# PR04.net
KiCad netlist of a schematic drawn in EAGLE
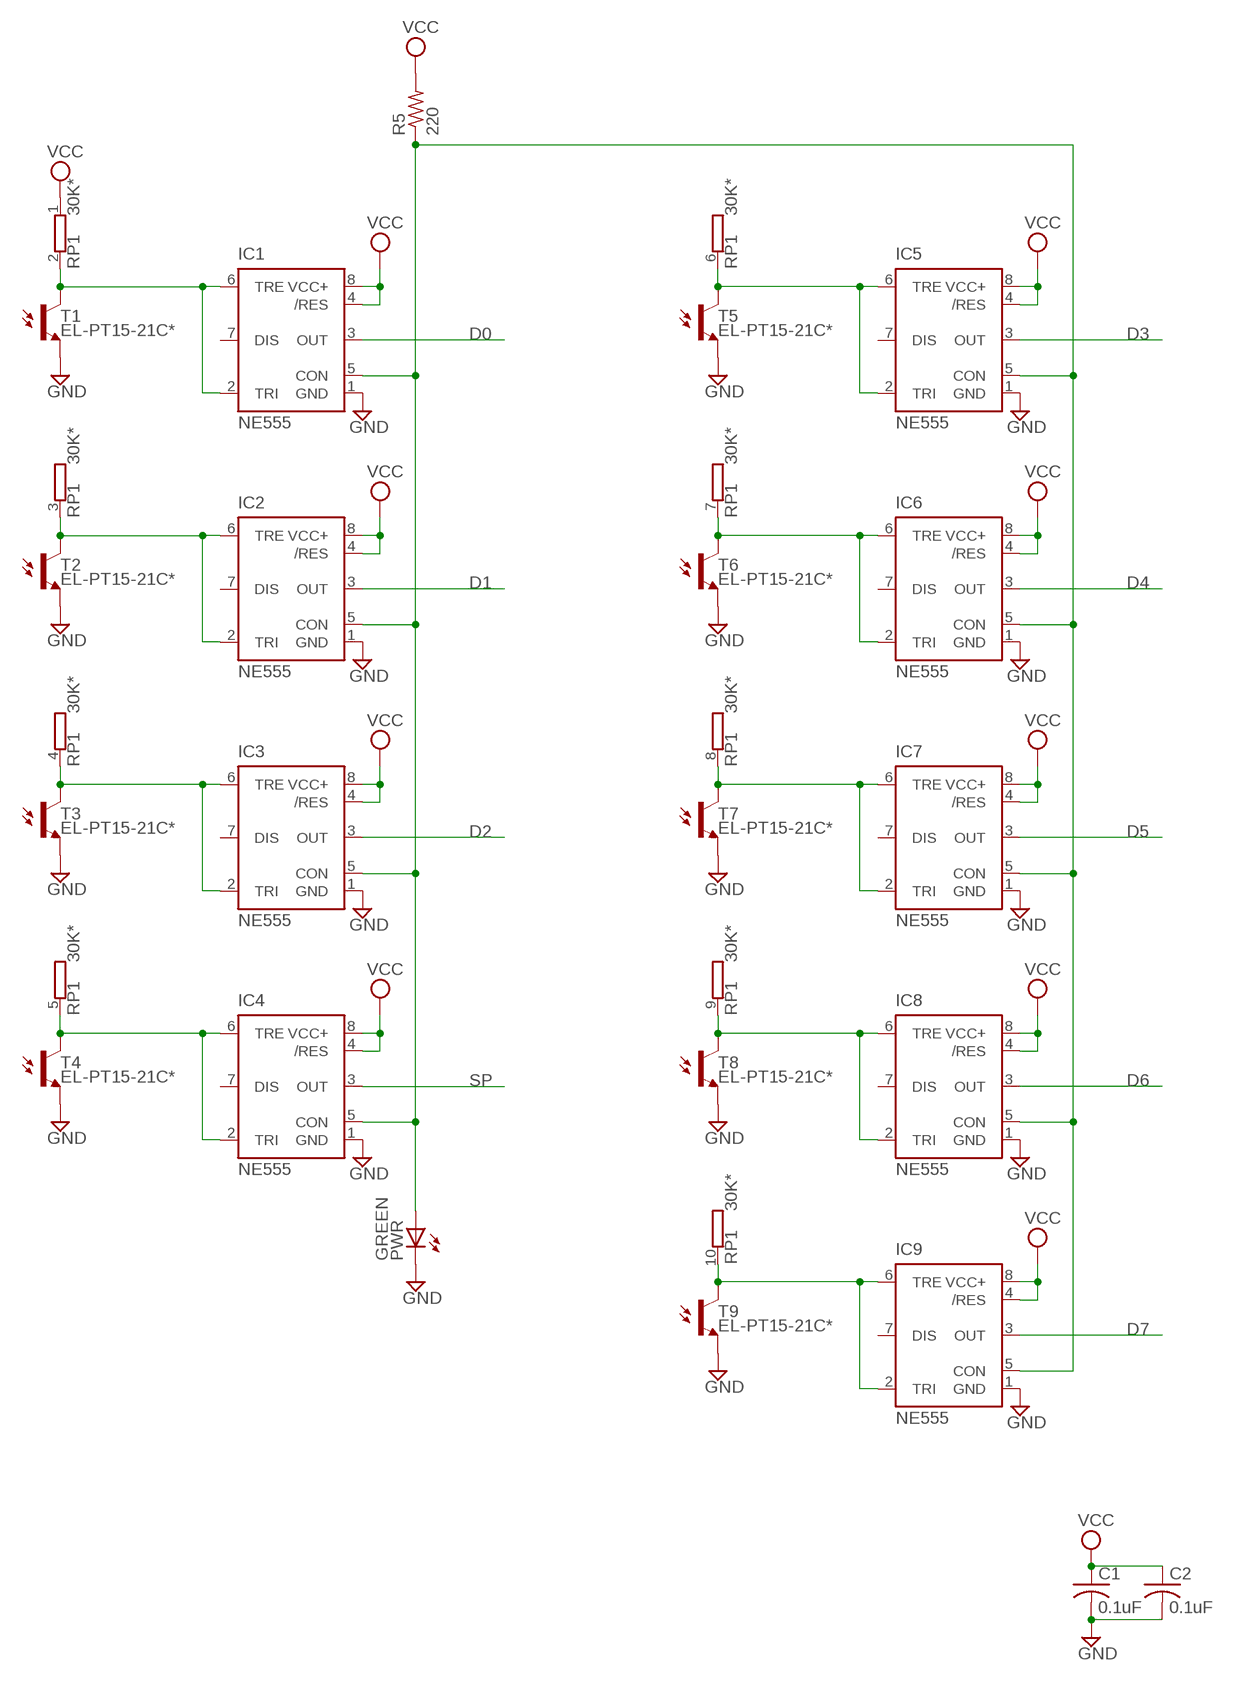
[diagram p0: schematic, sheet 1, part 1 of 2]
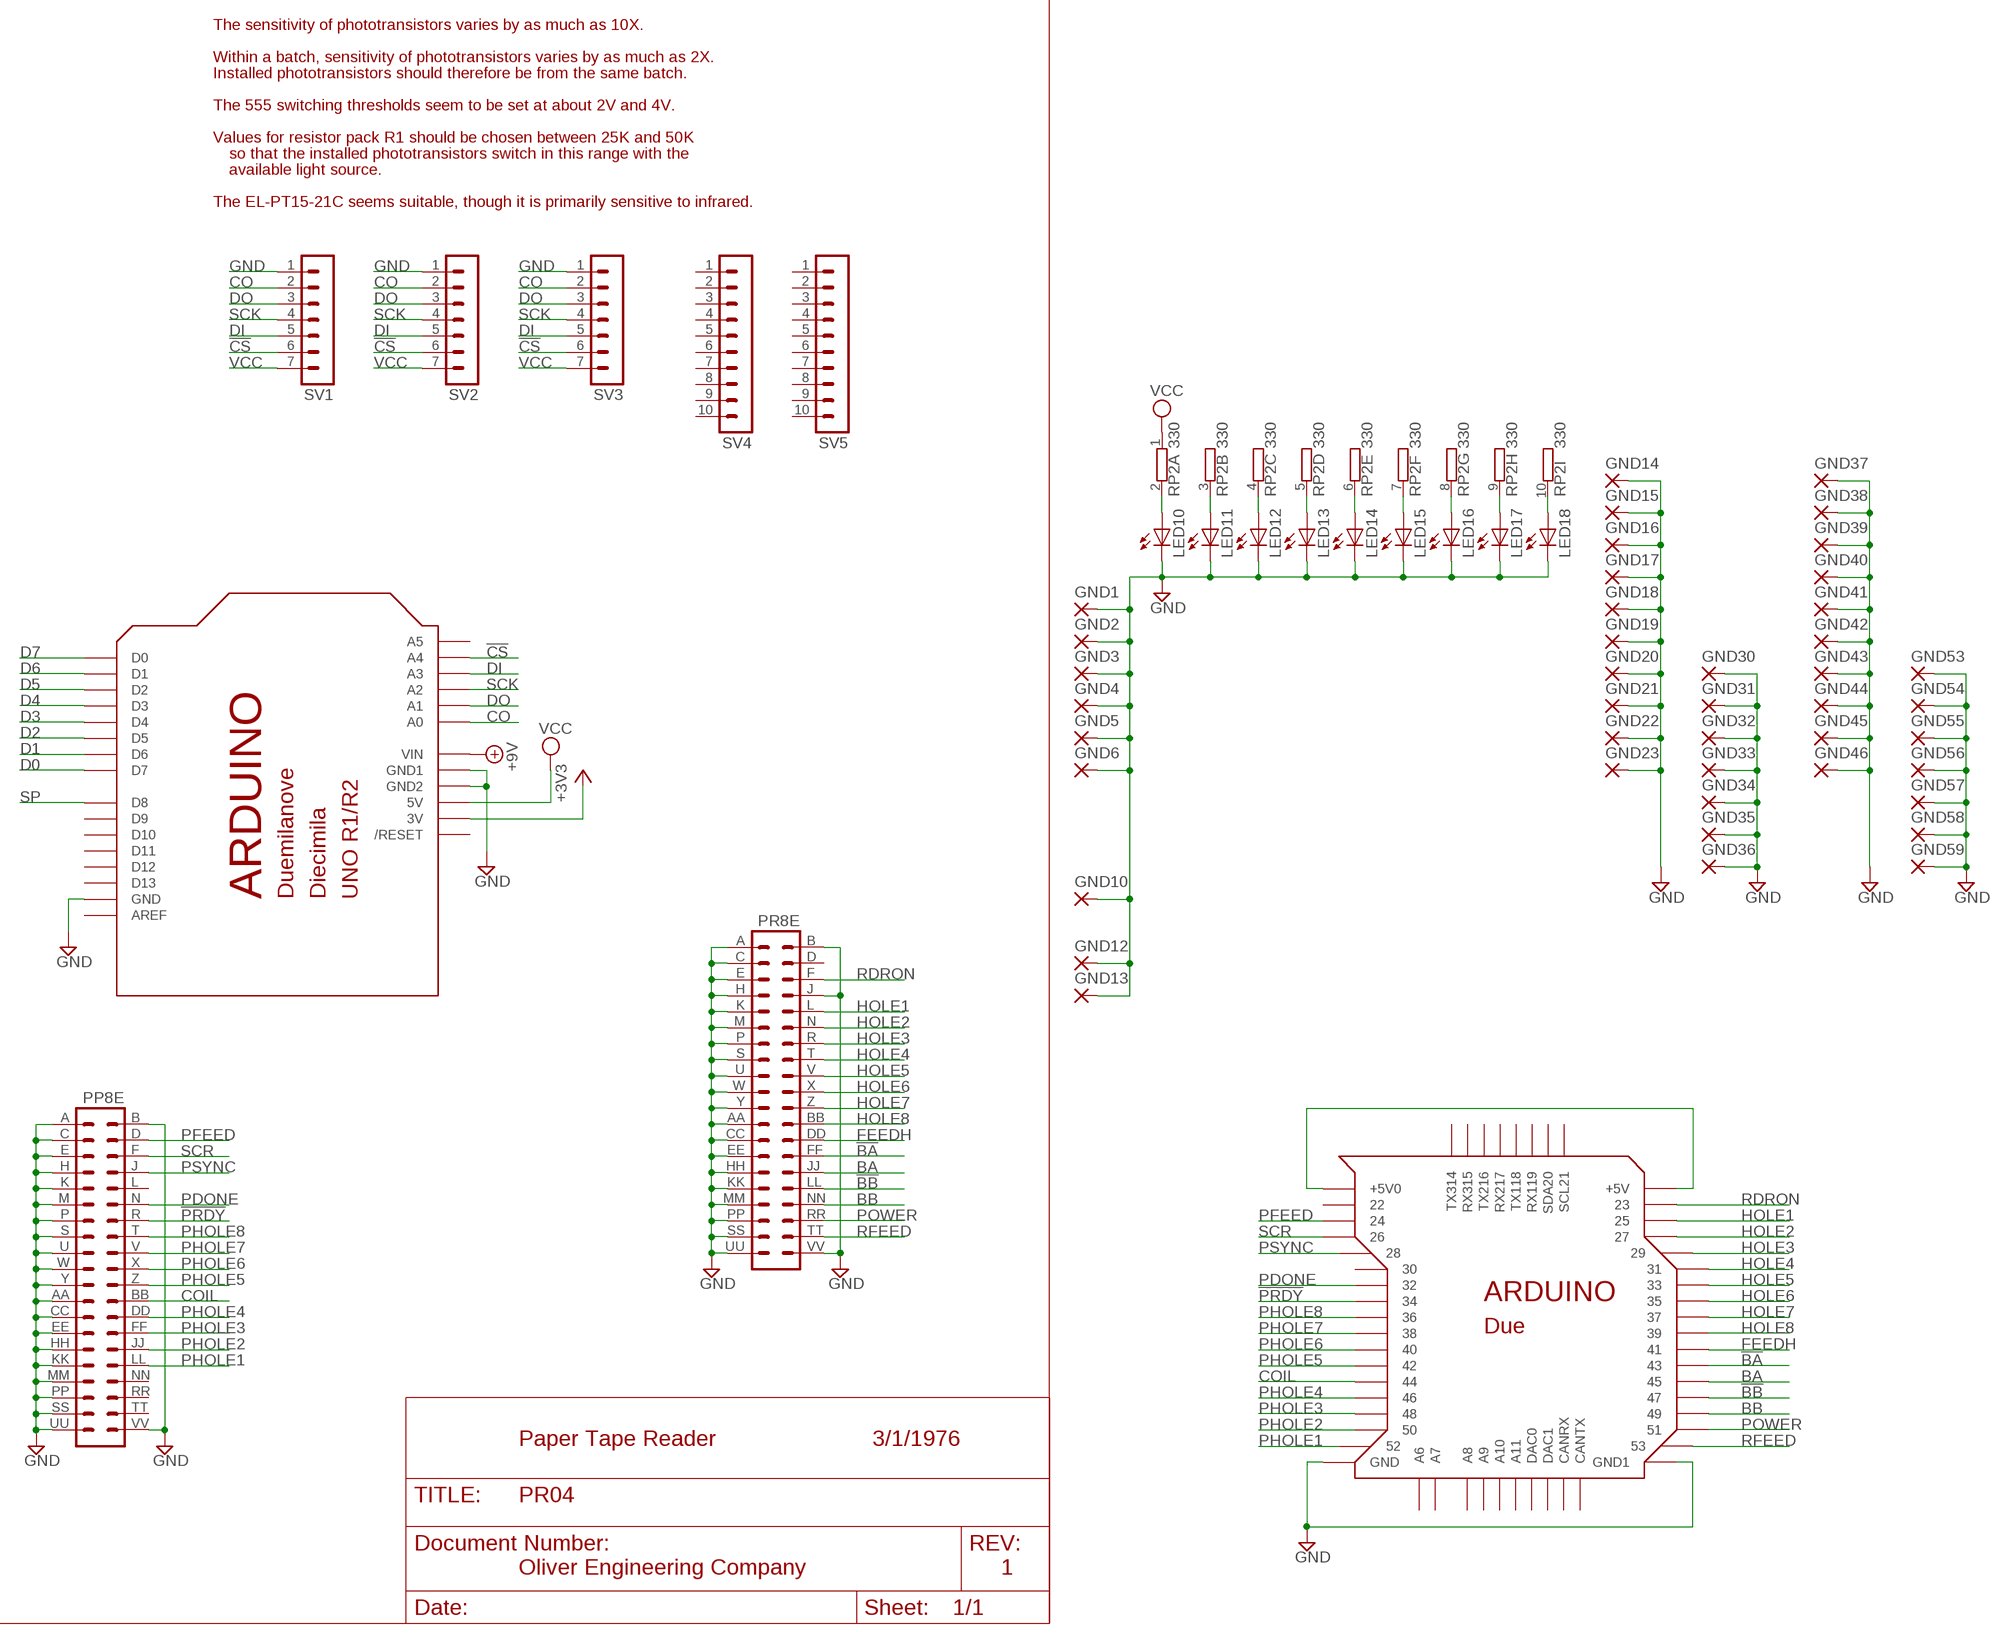
[diagram p1: schematic, sheet 1, part 2 of 2]

(export (version "E")
  (design (tool "Eeschema 10.0.6"))
  (components
    (comp (ref "C1")
      (value "0.1uF")
      (footprint "eagle-import:C050-030X075")
      (libsource (lib "eagle-import") (part "C-US050-030X075"))
    )
    (comp (ref "C2")
      (value "0.1uF")
      (footprint "eagle-import:C050-030X075")
      (libsource (lib "eagle-import") (part "C-US050-030X075"))
    )
    (comp (ref "GND1")
      (value "2,15/1,0")
      (footprint "eagle-import:2,15_1,0")
      (libsource (lib "eagle-import") (part "2,15/1,0"))
    )
    (comp (ref "GND2")
      (value "2,15/1,0")
      (footprint "eagle-import:2,15_1,0")
      (libsource (lib "eagle-import") (part "2,15/1,0"))
    )
    (comp (ref "GND3")
      (value "2,15/1,0")
      (footprint "eagle-import:2,15_1,0")
      (libsource (lib "eagle-import") (part "2,15/1,0"))
    )
    (comp (ref "GND4")
      (value "2,15/1,0")
      (footprint "eagle-import:2,15_1,0")
      (libsource (lib "eagle-import") (part "2,15/1,0"))
    )
    (comp (ref "GND5")
      (value "2,15/1,0")
      (footprint "eagle-import:2,15_1,0")
      (libsource (lib "eagle-import") (part "2,15/1,0"))
    )
    (comp (ref "GND6")
      (value "2,15/1,0")
      (footprint "eagle-import:2,15_1,0")
      (libsource (lib "eagle-import") (part "2,15/1,0"))
    )
    (comp (ref "GND10")
      (value "2,15/1,0")
      (footprint "eagle-import:2,15_1,0")
      (libsource (lib "eagle-import") (part "2,15/1,0"))
    )
    (comp (ref "GND12")
      (value "2,15/1,0")
      (footprint "eagle-import:2,15_1,0")
      (libsource (lib "eagle-import") (part "2,15/1,0"))
    )
    (comp (ref "GND13")
      (value "2,15/1,0")
      (footprint "eagle-import:2,15_1,0")
      (libsource (lib "eagle-import") (part "2,15/1,0"))
    )
    (comp (ref "GND14")
      (value "2,15/1,0")
      (footprint "eagle-import:2,15_1,0")
      (libsource (lib "eagle-import") (part "2,15/1,0"))
    )
    (comp (ref "GND15")
      (value "2,15/1,0")
      (footprint "eagle-import:2,15_1,0")
      (libsource (lib "eagle-import") (part "2,15/1,0"))
    )
    (comp (ref "GND16")
      (value "2,15/1,0")
      (footprint "eagle-import:2,15_1,0")
      (libsource (lib "eagle-import") (part "2,15/1,0"))
    )
    (comp (ref "GND17")
      (value "2,15/1,0")
      (footprint "eagle-import:2,15_1,0")
      (libsource (lib "eagle-import") (part "2,15/1,0"))
    )
    (comp (ref "GND18")
      (value "2,15/1,0")
      (footprint "eagle-import:2,15_1,0")
      (libsource (lib "eagle-import") (part "2,15/1,0"))
    )
    (comp (ref "GND19")
      (value "2,15/1,0")
      (footprint "eagle-import:2,15_1,0")
      (libsource (lib "eagle-import") (part "2,15/1,0"))
    )
    (comp (ref "GND20")
      (value "2,15/1,0")
      (footprint "eagle-import:2,15_1,0")
      (libsource (lib "eagle-import") (part "2,15/1,0"))
    )
    (comp (ref "GND21")
      (value "2,15/1,0")
      (footprint "eagle-import:2,15_1,0")
      (libsource (lib "eagle-import") (part "2,15/1,0"))
    )
    (comp (ref "GND22")
      (value "2,15/1,0")
      (footprint "eagle-import:2,15_1,0")
      (libsource (lib "eagle-import") (part "2,15/1,0"))
    )
    (comp (ref "GND23")
      (value "2,15/1,0")
      (footprint "eagle-import:2,15_1,0")
      (libsource (lib "eagle-import") (part "2,15/1,0"))
    )
    (comp (ref "GND30")
      (value "2,15/1,0")
      (footprint "eagle-import:2,15_1,0")
      (libsource (lib "eagle-import") (part "2,15/1,0"))
    )
    (comp (ref "GND31")
      (value "2,15/1,0")
      (footprint "eagle-import:2,15_1,0")
      (libsource (lib "eagle-import") (part "2,15/1,0"))
    )
    (comp (ref "GND32")
      (value "2,15/1,0")
      (footprint "eagle-import:2,15_1,0")
      (libsource (lib "eagle-import") (part "2,15/1,0"))
    )
    (comp (ref "GND33")
      (value "2,15/1,0")
      (footprint "eagle-import:2,15_1,0")
      (libsource (lib "eagle-import") (part "2,15/1,0"))
    )
    (comp (ref "GND34")
      (value "2,15/1,0")
      (footprint "eagle-import:2,15_1,0")
      (libsource (lib "eagle-import") (part "2,15/1,0"))
    )
    (comp (ref "GND35")
      (value "2,15/1,0")
      (footprint "eagle-import:2,15_1,0")
      (libsource (lib "eagle-import") (part "2,15/1,0"))
    )
    (comp (ref "GND36")
      (value "2,15/1,0")
      (footprint "eagle-import:2,15_1,0")
      (libsource (lib "eagle-import") (part "2,15/1,0"))
    )
    (comp (ref "GND37")
      (value "2,15/1,0")
      (footprint "eagle-import:2,15_1,0")
      (libsource (lib "eagle-import") (part "2,15/1,0"))
    )
    (comp (ref "GND38")
      (value "2,15/1,0")
      (footprint "eagle-import:2,15_1,0")
      (libsource (lib "eagle-import") (part "2,15/1,0"))
    )
    (comp (ref "GND39")
      (value "2,15/1,0")
      (footprint "eagle-import:2,15_1,0")
      (libsource (lib "eagle-import") (part "2,15/1,0"))
    )
    (comp (ref "GND40")
      (value "2,15/1,0")
      (footprint "eagle-import:2,15_1,0")
      (libsource (lib "eagle-import") (part "2,15/1,0"))
    )
    (comp (ref "GND41")
      (value "2,15/1,0")
      (footprint "eagle-import:2,15_1,0")
      (libsource (lib "eagle-import") (part "2,15/1,0"))
    )
    (comp (ref "GND42")
      (value "2,15/1,0")
      (footprint "eagle-import:2,15_1,0")
      (libsource (lib "eagle-import") (part "2,15/1,0"))
    )
    (comp (ref "GND43")
      (value "2,15/1,0")
      (footprint "eagle-import:2,15_1,0")
      (libsource (lib "eagle-import") (part "2,15/1,0"))
    )
    (comp (ref "GND44")
      (value "2,15/1,0")
      (footprint "eagle-import:2,15_1,0")
      (libsource (lib "eagle-import") (part "2,15/1,0"))
    )
    (comp (ref "GND45")
      (value "2,15/1,0")
      (footprint "eagle-import:2,15_1,0")
      (libsource (lib "eagle-import") (part "2,15/1,0"))
    )
    (comp (ref "GND46")
      (value "2,15/1,0")
      (footprint "eagle-import:2,15_1,0")
      (libsource (lib "eagle-import") (part "2,15/1,0"))
    )
    (comp (ref "GND53")
      (value "2,15/1,0")
      (footprint "eagle-import:2,15_1,0")
      (libsource (lib "eagle-import") (part "2,15/1,0"))
    )
    (comp (ref "GND54")
      (value "2,15/1,0")
      (footprint "eagle-import:2,15_1,0")
      (libsource (lib "eagle-import") (part "2,15/1,0"))
    )
    (comp (ref "GND55")
      (value "2,15/1,0")
      (footprint "eagle-import:2,15_1,0")
      (libsource (lib "eagle-import") (part "2,15/1,0"))
    )
    (comp (ref "GND56")
      (value "2,15/1,0")
      (footprint "eagle-import:2,15_1,0")
      (libsource (lib "eagle-import") (part "2,15/1,0"))
    )
    (comp (ref "GND57")
      (value "2,15/1,0")
      (footprint "eagle-import:2,15_1,0")
      (libsource (lib "eagle-import") (part "2,15/1,0"))
    )
    (comp (ref "GND58")
      (value "2,15/1,0")
      (footprint "eagle-import:2,15_1,0")
      (libsource (lib "eagle-import") (part "2,15/1,0"))
    )
    (comp (ref "GND59")
      (value "2,15/1,0")
      (footprint "eagle-import:2,15_1,0")
      (libsource (lib "eagle-import") (part "2,15/1,0"))
    )
    (comp (ref "IC1")
      (value "NE555")
      (footprint "eagle-import:DIL-08")
      (fields (field (name "MF") "Arrow Electronics") (field (name "MPN") "NE555N"))
      (libsource (lib "eagle-import") (part "NE555"))
    )
    (comp (ref "IC2")
      (value "NE555")
      (footprint "eagle-import:DIL-08")
      (fields (field (name "MF") "Arrow Electronics") (field (name "MPN") "NE555N"))
      (libsource (lib "eagle-import") (part "NE555"))
    )
    (comp (ref "IC3")
      (value "NE555")
      (footprint "eagle-import:DIL-08")
      (fields (field (name "MF") "Arrow Electronics") (field (name "MPN") "NE555N"))
      (libsource (lib "eagle-import") (part "NE555"))
    )
    (comp (ref "IC4")
      (value "NE555")
      (footprint "eagle-import:DIL-08")
      (fields (field (name "MF") "Arrow Electronics") (field (name "MPN") "NE555N"))
      (libsource (lib "eagle-import") (part "NE555"))
    )
    (comp (ref "IC5")
      (value "NE555")
      (footprint "eagle-import:DIL-08")
      (fields (field (name "MF") "Arrow Electronics") (field (name "MPN") "NE555N"))
      (libsource (lib "eagle-import") (part "NE555"))
    )
    (comp (ref "IC6")
      (value "NE555")
      (footprint "eagle-import:DIL-08")
      (fields (field (name "MF") "Arrow Electronics") (field (name "MPN") "NE555N"))
      (libsource (lib "eagle-import") (part "NE555"))
    )
    (comp (ref "IC7")
      (value "NE555")
      (footprint "eagle-import:DIL-08")
      (fields (field (name "MF") "Arrow Electronics") (field (name "MPN") "NE555N"))
      (libsource (lib "eagle-import") (part "NE555"))
    )
    (comp (ref "IC8")
      (value "NE555")
      (footprint "eagle-import:DIL-08")
      (fields (field (name "MF") "Arrow Electronics") (field (name "MPN") "NE555N"))
      (libsource (lib "eagle-import") (part "NE555"))
    )
    (comp (ref "IC9")
      (value "NE555")
      (footprint "eagle-import:DIL-08")
      (fields (field (name "MF") "Arrow Electronics") (field (name "MPN") "NE555N"))
      (libsource (lib "eagle-import") (part "NE555"))
    )
    (comp (ref "LED10")
      (value "LEDCHIPLED_1206")
      (footprint "eagle-import:CHIPLED_1206")
      (libsource (lib "eagle-import") (part "opto_LEDCHIPLED_1206"))
    )
    (comp (ref "LED11")
      (value "LEDCHIPLED_1206")
      (footprint "eagle-import:CHIPLED_1206")
      (libsource (lib "eagle-import") (part "opto_LEDCHIPLED_1206"))
    )
    (comp (ref "LED12")
      (value "LEDCHIPLED_1206")
      (footprint "eagle-import:CHIPLED_1206")
      (libsource (lib "eagle-import") (part "opto_LEDCHIPLED_1206"))
    )
    (comp (ref "LED13")
      (value "LEDCHIPLED_1206")
      (footprint "eagle-import:CHIPLED_1206")
      (libsource (lib "eagle-import") (part "opto_LEDCHIPLED_1206"))
    )
    (comp (ref "LED14")
      (value "LEDCHIPLED_1206")
      (footprint "eagle-import:CHIPLED_1206")
      (libsource (lib "eagle-import") (part "opto_LEDCHIPLED_1206"))
    )
    (comp (ref "LED15")
      (value "LEDCHIPLED_1206")
      (footprint "eagle-import:CHIPLED_1206")
      (libsource (lib "eagle-import") (part "opto_LEDCHIPLED_1206"))
    )
    (comp (ref "LED16")
      (value "LEDCHIPLED_1206")
      (footprint "eagle-import:CHIPLED_1206")
      (libsource (lib "eagle-import") (part "opto_LEDCHIPLED_1206"))
    )
    (comp (ref "LED17")
      (value "LEDCHIPLED_1206")
      (footprint "eagle-import:CHIPLED_1206")
      (libsource (lib "eagle-import") (part "opto_LEDCHIPLED_1206"))
    )
    (comp (ref "LED18")
      (value "LEDCHIPLED_1206")
      (footprint "eagle-import:CHIPLED_1206")
      (libsource (lib "eagle-import") (part "opto_LEDCHIPLED_1206"))
    )
    (comp (ref "PP8E")
      (value "DEC40PINV")
      (footprint "eagle-import:DEC40PINV")
      (libsource (lib "eagle-import") (part "DEC40PINV"))
    )
    (comp (ref "PR8E")
      (value "DEC40PINV")
      (footprint "eagle-import:DEC40PINV")
      (libsource (lib "eagle-import") (part "DEC40PINV"))
    )
    (comp (ref "PWR")
      (value "GREEN")
      (footprint "eagle-import:LED3MM")
      (libsource (lib "eagle-import") (part "LED3MM"))
    )
    (comp (ref "R5")
      (value "220")
      (footprint "eagle-import:0207_10")
      (libsource (lib "eagle-import") (part "R-US_0207/10"))
    )
    (comp (ref "RP1")
      (value "30K*")
      (footprint "eagle-import:SIL10")
      (libsource (lib "eagle-import") (part "GE09RP"))
    )
    (comp (ref "RP2")
      (value "330")
      (footprint "eagle-import:SIL10")
      (libsource (lib "eagle-import") (part "GE09R"))
    )
    (comp (ref "SV1")
      (value "MA07-1")
      (footprint "eagle-import:MA07-1")
      (libsource (lib "eagle-import") (part "MA07-1"))
    )
    (comp (ref "SV2")
      (value "MA07-1")
      (footprint "eagle-import:MA07-1")
      (libsource (lib "eagle-import") (part "MA07-1"))
    )
    (comp (ref "SV3")
      (value "MA07-1")
      (footprint "eagle-import:MA07-1")
      (libsource (lib "eagle-import") (part "MA07-1"))
    )
    (comp (ref "SV4")
      (value "MA10-1")
      (footprint "eagle-import:MA10-1")
      (libsource (lib "eagle-import") (part "MA10-1"))
    )
    (comp (ref "SV5")
      (value "MA10-1")
      (footprint "eagle-import:MA10-1")
      (libsource (lib "eagle-import") (part "MA10-1"))
    )
    (comp (ref "T1")
      (value "EL-PT15-21C*")
      (footprint "eagle-import:CHIPLED_1206")
      (libsource (lib "eagle-import") (part "PHOTOTRANSISTOR"))
    )
    (comp (ref "T2")
      (value "EL-PT15-21C*")
      (footprint "eagle-import:CHIPLED_1206")
      (libsource (lib "eagle-import") (part "PHOTOTRANSISTOR"))
    )
    (comp (ref "T3")
      (value "EL-PT15-21C*")
      (footprint "eagle-import:CHIPLED_1206")
      (libsource (lib "eagle-import") (part "PHOTOTRANSISTOR"))
    )
    (comp (ref "T4")
      (value "EL-PT15-21C*")
      (footprint "eagle-import:CHIPLED_1206")
      (libsource (lib "eagle-import") (part "PHOTOTRANSISTOR"))
    )
    (comp (ref "T5")
      (value "EL-PT15-21C*")
      (footprint "eagle-import:CHIPLED_1206")
      (libsource (lib "eagle-import") (part "PHOTOTRANSISTOR"))
    )
    (comp (ref "T6")
      (value "EL-PT15-21C*")
      (footprint "eagle-import:CHIPLED_1206")
      (libsource (lib "eagle-import") (part "PHOTOTRANSISTOR"))
    )
    (comp (ref "T7")
      (value "EL-PT15-21C*")
      (footprint "eagle-import:CHIPLED_1206")
      (libsource (lib "eagle-import") (part "PHOTOTRANSISTOR"))
    )
    (comp (ref "T8")
      (value "EL-PT15-21C*")
      (footprint "eagle-import:CHIPLED_1206")
      (libsource (lib "eagle-import") (part "PHOTOTRANSISTOR"))
    )
    (comp (ref "T9")
      (value "EL-PT15-21C*")
      (footprint "eagle-import:CHIPLED_1206")
      (libsource (lib "eagle-import") (part "PHOTOTRANSISTOR"))
    )
    (comp (ref "U$2")
      (value "ARDUINO-X")
      (footprint "eagle-import:ARDUINO_DUE_SHIELD")
      (libsource (lib "eagle-import") (part "ARDUINO-X"))
    )
  )
  (nets
    (net (code "1") (name "+3V3") (class "Default")
      (node (ref "U$2") (pin "3V3") (pinfunction "3V_3V3") (pintype "power_in"))
    )
    (net (code "2") (name "+9V") (class "Default")
      (node (ref "U$2") (pin "VIN") (pinfunction "VIN_VIN") (pintype "power_in"))
    )
    (net (code "3") (name "/BA") (class "Default")
      (node (ref "PR8E") (pin "JJ") (pinfunction "30_JJ") (pintype "bidirectional"))
      (node (ref "U$2") (pin "45") (pinfunction "45_45") (pintype "bidirectional"))
    )
    (net (code "4") (name "/BB") (class "Default")
      (node (ref "PR8E") (pin "NN") (pinfunction "34_NN") (pintype "bidirectional"))
      (node (ref "U$2") (pin "49") (pinfunction "49_49") (pintype "bidirectional"))
    )
    (net (code "5") (name "/CO") (class "Default")
      (node (ref "SV1") (pin "2") (pinfunction "2_2") (pintype "passive"))
      (node (ref "SV2") (pin "2") (pinfunction "2_2") (pintype "passive"))
      (node (ref "SV3") (pin "2") (pinfunction "2_2") (pintype "passive"))
      (node (ref "U$2") (pin "A0") (pinfunction "A0_A0") (pintype "bidirectional"))
    )
    (net (code "6") (name "/COIL") (class "Default")
      (node (ref "PP8E") (pin "BB") (pinfunction "24_BB") (pintype "bidirectional"))
      (node (ref "U$2") (pin "44") (pinfunction "44_44") (pintype "bidirectional"))
    )
    (net (code "7") (name "/D0") (class "Default")
      (node (ref "IC1") (pin "3") (pinfunction "OUT_3") (pintype "output"))
      (node (ref "U$2") (pin "7") (pinfunction "D7_7") (pintype "bidirectional"))
    )
    (net (code "8") (name "/D1") (class "Default")
      (node (ref "IC2") (pin "3") (pinfunction "OUT_3") (pintype "output"))
      (node (ref "U$2") (pin "6") (pinfunction "D6_6") (pintype "bidirectional"))
    )
    (net (code "9") (name "/D2") (class "Default")
      (node (ref "IC3") (pin "3") (pinfunction "OUT_3") (pintype "output"))
      (node (ref "U$2") (pin "5") (pinfunction "D5_5") (pintype "bidirectional"))
    )
    (net (code "10") (name "/D3") (class "Default")
      (node (ref "IC5") (pin "3") (pinfunction "OUT_3") (pintype "output"))
      (node (ref "U$2") (pin "4") (pinfunction "D4_4") (pintype "bidirectional"))
    )
    (net (code "11") (name "/D4") (class "Default")
      (node (ref "IC6") (pin "3") (pinfunction "OUT_3") (pintype "output"))
      (node (ref "U$2") (pin "3") (pinfunction "D3_3") (pintype "bidirectional"))
    )
    (net (code "12") (name "/D5") (class "Default")
      (node (ref "IC7") (pin "3") (pinfunction "OUT_3") (pintype "output"))
      (node (ref "U$2") (pin "2") (pinfunction "D2_2") (pintype "bidirectional"))
    )
    (net (code "13") (name "/D6") (class "Default")
      (node (ref "IC8") (pin "3") (pinfunction "OUT_3") (pintype "output"))
      (node (ref "U$2") (pin "1") (pinfunction "D1_1") (pintype "bidirectional"))
    )
    (net (code "14") (name "/D7") (class "Default")
      (node (ref "IC9") (pin "3") (pinfunction "OUT_3") (pintype "output"))
      (node (ref "U$2") (pin "0") (pinfunction "D0_0") (pintype "bidirectional"))
    )
    (net (code "15") (name "/DI") (class "Default")
      (node (ref "SV1") (pin "5") (pinfunction "5_5") (pintype "passive"))
      (node (ref "SV2") (pin "5") (pinfunction "5_5") (pintype "passive"))
      (node (ref "SV3") (pin "5") (pinfunction "5_5") (pintype "passive"))
      (node (ref "U$2") (pin "A3") (pinfunction "A3_A3") (pintype "bidirectional"))
    )
    (net (code "16") (name "/DO") (class "Default")
      (node (ref "SV1") (pin "3") (pinfunction "3_3") (pintype "passive"))
      (node (ref "SV2") (pin "3") (pinfunction "3_3") (pintype "passive"))
      (node (ref "SV3") (pin "3") (pinfunction "3_3") (pintype "passive"))
      (node (ref "U$2") (pin "A1") (pinfunction "A1_A1") (pintype "bidirectional"))
    )
    (net (code "17") (name "/FEEDH") (class "Default")
      (node (ref "PR8E") (pin "DD") (pinfunction "26_DD") (pintype "bidirectional"))
      (node (ref "U$2") (pin "41") (pinfunction "41_41") (pintype "bidirectional"))
    )
    (net (code "18") (name "/HOLE1") (class "Default")
      (node (ref "PR8E") (pin "L") (pinfunction "10_L") (pintype "bidirectional"))
      (node (ref "U$2") (pin "25") (pinfunction "25_25") (pintype "bidirectional"))
    )
    (net (code "19") (name "/HOLE2") (class "Default")
      (node (ref "PR8E") (pin "N") (pinfunction "12_N") (pintype "bidirectional"))
      (node (ref "U$2") (pin "27") (pinfunction "27_27") (pintype "bidirectional"))
    )
    (net (code "20") (name "/HOLE3") (class "Default")
      (node (ref "PR8E") (pin "R") (pinfunction "14_R") (pintype "bidirectional"))
      (node (ref "U$2") (pin "29") (pinfunction "29_29") (pintype "bidirectional"))
    )
    (net (code "21") (name "/HOLE4") (class "Default")
      (node (ref "PR8E") (pin "T") (pinfunction "16_T") (pintype "bidirectional"))
      (node (ref "U$2") (pin "31") (pinfunction "31_31") (pintype "bidirectional"))
    )
    (net (code "22") (name "/HOLE5") (class "Default")
      (node (ref "PR8E") (pin "V") (pinfunction "18_V") (pintype "bidirectional"))
      (node (ref "U$2") (pin "33") (pinfunction "33_33") (pintype "bidirectional"))
    )
    (net (code "23") (name "/HOLE6") (class "Default")
      (node (ref "PR8E") (pin "X") (pinfunction "20_X") (pintype "bidirectional"))
      (node (ref "U$2") (pin "35") (pinfunction "35_35") (pintype "bidirectional"))
    )
    (net (code "24") (name "/HOLE7") (class "Default")
      (node (ref "PR8E") (pin "Z") (pinfunction "22_Z") (pintype "bidirectional"))
      (node (ref "U$2") (pin "37") (pinfunction "37_37") (pintype "bidirectional"))
    )
    (net (code "25") (name "/HOLE8") (class "Default")
      (node (ref "PR8E") (pin "BB") (pinfunction "24_BB") (pintype "bidirectional"))
      (node (ref "U$2") (pin "39") (pinfunction "39_39") (pintype "bidirectional"))
    )
    (net (code "26") (name "/PDONE") (class "Default")
      (node (ref "PP8E") (pin "N") (pinfunction "12_N") (pintype "bidirectional"))
      (node (ref "U$2") (pin "32") (pinfunction "32_32") (pintype "bidirectional"))
    )
    (net (code "27") (name "/PFEED") (class "Default")
      (node (ref "PP8E") (pin "D") (pinfunction "4_D") (pintype "bidirectional"))
      (node (ref "U$2") (pin "24") (pinfunction "24_24") (pintype "bidirectional"))
    )
    (net (code "28") (name "/PHOLE1") (class "Default")
      (node (ref "PP8E") (pin "LL") (pinfunction "32_LL") (pintype "bidirectional"))
      (node (ref "U$2") (pin "52") (pinfunction "52_52") (pintype "bidirectional"))
    )
    (net (code "29") (name "/PHOLE2") (class "Default")
      (node (ref "PP8E") (pin "JJ") (pinfunction "30_JJ") (pintype "bidirectional"))
      (node (ref "U$2") (pin "50") (pinfunction "50_50") (pintype "bidirectional"))
    )
    (net (code "30") (name "/PHOLE3") (class "Default")
      (node (ref "PP8E") (pin "FF") (pinfunction "28_FF") (pintype "bidirectional"))
      (node (ref "U$2") (pin "48") (pinfunction "48_48") (pintype "bidirectional"))
    )
    (net (code "31") (name "/PHOLE4") (class "Default")
      (node (ref "PP8E") (pin "DD") (pinfunction "26_DD") (pintype "bidirectional"))
      (node (ref "U$2") (pin "46") (pinfunction "46_46") (pintype "bidirectional"))
    )
    (net (code "32") (name "/PHOLE5") (class "Default")
      (node (ref "PP8E") (pin "Z") (pinfunction "22_Z") (pintype "bidirectional"))
      (node (ref "U$2") (pin "42") (pinfunction "42_42") (pintype "bidirectional"))
    )
    (net (code "33") (name "/PHOLE6") (class "Default")
      (node (ref "PP8E") (pin "X") (pinfunction "20_X") (pintype "bidirectional"))
      (node (ref "U$2") (pin "40") (pinfunction "40_40") (pintype "bidirectional"))
    )
    (net (code "34") (name "/PHOLE7") (class "Default")
      (node (ref "PP8E") (pin "V") (pinfunction "18_V") (pintype "bidirectional"))
      (node (ref "U$2") (pin "38") (pinfunction "38_38") (pintype "bidirectional"))
    )
    (net (code "35") (name "/PHOLE8") (class "Default")
      (node (ref "PP8E") (pin "T") (pinfunction "16_T") (pintype "bidirectional"))
      (node (ref "U$2") (pin "36") (pinfunction "36_36") (pintype "bidirectional"))
    )
    (net (code "36") (name "/POWER") (class "Default")
      (node (ref "PR8E") (pin "RR") (pinfunction "36_RR") (pintype "bidirectional"))
      (node (ref "U$2") (pin "51") (pinfunction "51_51") (pintype "bidirectional"))
    )
    (net (code "37") (name "/PSYNC") (class "Default")
      (node (ref "PP8E") (pin "J") (pinfunction "8_J") (pintype "bidirectional"))
      (node (ref "U$2") (pin "28") (pinfunction "28_28") (pintype "bidirectional"))
    )
    (net (code "38") (name "/RDRON") (class "Default")
      (node (ref "PR8E") (pin "F") (pinfunction "6_F") (pintype "bidirectional"))
      (node (ref "U$2") (pin "23") (pinfunction "23_23") (pintype "bidirectional"))
    )
    (net (code "39") (name "/RFEED") (class "Default")
      (node (ref "PR8E") (pin "TT") (pinfunction "38_TT") (pintype "bidirectional"))
      (node (ref "U$2") (pin "53") (pinfunction "53_53") (pintype "bidirectional"))
    )
    (net (code "40") (name "/SCK") (class "Default")
      (node (ref "SV1") (pin "4") (pinfunction "4_4") (pintype "passive"))
      (node (ref "SV2") (pin "4") (pinfunction "4_4") (pintype "passive"))
      (node (ref "SV3") (pin "4") (pinfunction "4_4") (pintype "passive"))
      (node (ref "U$2") (pin "A2") (pinfunction "A2_A2") (pintype "bidirectional"))
    )
    (net (code "41") (name "/SCR") (class "Default")
      (node (ref "PP8E") (pin "F") (pinfunction "6_F") (pintype "bidirectional"))
      (node (ref "U$2") (pin "26") (pinfunction "26_26") (pintype "bidirectional"))
    )
    (net (code "42") (name "/SP") (class "Default")
      (node (ref "IC4") (pin "3") (pinfunction "OUT_3") (pintype "output"))
      (node (ref "U$2") (pin "8") (pinfunction "D8_8") (pintype "bidirectional"))
    )
    (net (code "43") (name "/~{BA}") (class "Default")
      (node (ref "PR8E") (pin "FF") (pinfunction "28_FF") (pintype "bidirectional"))
      (node (ref "U$2") (pin "43") (pinfunction "43_43") (pintype "bidirectional"))
    )
    (net (code "44") (name "/~{BB}") (class "Default")
      (node (ref "PR8E") (pin "LL") (pinfunction "32_LL") (pintype "bidirectional"))
      (node (ref "U$2") (pin "47") (pinfunction "47_47") (pintype "bidirectional"))
    )
    (net (code "45") (name "/~{CS}") (class "Default")
      (node (ref "SV1") (pin "6") (pinfunction "6_6") (pintype "passive"))
      (node (ref "SV2") (pin "6") (pinfunction "6_6") (pintype "passive"))
      (node (ref "SV3") (pin "6") (pinfunction "6_6") (pintype "passive"))
      (node (ref "U$2") (pin "A4") (pinfunction "A4_A4") (pintype "bidirectional"))
    )
    (net (code "46") (name "/~{PRDY}") (class "Default")
      (node (ref "PP8E") (pin "R") (pinfunction "14_R") (pintype "bidirectional"))
      (node (ref "U$2") (pin "34") (pinfunction "34_34") (pintype "bidirectional"))
    )
    (net (code "47") (name "GND") (class "Default")
      (node (ref "C1") (pin "2") (pinfunction "2_2") (pintype "passive"))
      (node (ref "C2") (pin "2") (pinfunction "2_2") (pintype "passive"))
      (node (ref "GND1") (pin "1") (pinfunction "P_1") (pintype "passive"))
      (node (ref "GND10") (pin "1") (pinfunction "P_1") (pintype "passive"))
      (node (ref "GND12") (pin "1") (pinfunction "P_1") (pintype "passive"))
      (node (ref "GND13") (pin "1") (pinfunction "P_1") (pintype "passive"))
      (node (ref "GND14") (pin "1") (pinfunction "P_1") (pintype "passive"))
      (node (ref "GND15") (pin "1") (pinfunction "P_1") (pintype "passive"))
      (node (ref "GND16") (pin "1") (pinfunction "P_1") (pintype "passive"))
      (node (ref "GND17") (pin "1") (pinfunction "P_1") (pintype "passive"))
      (node (ref "GND18") (pin "1") (pinfunction "P_1") (pintype "passive"))
      (node (ref "GND19") (pin "1") (pinfunction "P_1") (pintype "passive"))
      (node (ref "GND2") (pin "1") (pinfunction "P_1") (pintype "passive"))
      (node (ref "GND20") (pin "1") (pinfunction "P_1") (pintype "passive"))
      (node (ref "GND21") (pin "1") (pinfunction "P_1") (pintype "passive"))
      (node (ref "GND22") (pin "1") (pinfunction "P_1") (pintype "passive"))
      (node (ref "GND23") (pin "1") (pinfunction "P_1") (pintype "passive"))
      (node (ref "GND3") (pin "1") (pinfunction "P_1") (pintype "passive"))
      (node (ref "GND30") (pin "1") (pinfunction "P_1") (pintype "passive"))
      (node (ref "GND31") (pin "1") (pinfunction "P_1") (pintype "passive"))
      (node (ref "GND32") (pin "1") (pinfunction "P_1") (pintype "passive"))
      (node (ref "GND33") (pin "1") (pinfunction "P_1") (pintype "passive"))
      (node (ref "GND34") (pin "1") (pinfunction "P_1") (pintype "passive"))
      (node (ref "GND35") (pin "1") (pinfunction "P_1") (pintype "passive"))
      (node (ref "GND36") (pin "1") (pinfunction "P_1") (pintype "passive"))
      (node (ref "GND37") (pin "1") (pinfunction "P_1") (pintype "passive"))
      (node (ref "GND38") (pin "1") (pinfunction "P_1") (pintype "passive"))
      (node (ref "GND39") (pin "1") (pinfunction "P_1") (pintype "passive"))
      (node (ref "GND4") (pin "1") (pinfunction "P_1") (pintype "passive"))
      (node (ref "GND40") (pin "1") (pinfunction "P_1") (pintype "passive"))
      (node (ref "GND41") (pin "1") (pinfunction "P_1") (pintype "passive"))
      (node (ref "GND42") (pin "1") (pinfunction "P_1") (pintype "passive"))
      (node (ref "GND43") (pin "1") (pinfunction "P_1") (pintype "passive"))
      (node (ref "GND44") (pin "1") (pinfunction "P_1") (pintype "passive"))
      (node (ref "GND45") (pin "1") (pinfunction "P_1") (pintype "passive"))
      (node (ref "GND46") (pin "1") (pinfunction "P_1") (pintype "passive"))
      (node (ref "GND5") (pin "1") (pinfunction "P_1") (pintype "passive"))
      (node (ref "GND53") (pin "1") (pinfunction "P_1") (pintype "passive"))
      (node (ref "GND54") (pin "1") (pinfunction "P_1") (pintype "passive"))
      (node (ref "GND55") (pin "1") (pinfunction "P_1") (pintype "passive"))
      (node (ref "GND56") (pin "1") (pinfunction "P_1") (pintype "passive"))
      (node (ref "GND57") (pin "1") (pinfunction "P_1") (pintype "passive"))
      (node (ref "GND58") (pin "1") (pinfunction "P_1") (pintype "passive"))
      (node (ref "GND59") (pin "1") (pinfunction "P_1") (pintype "passive"))
      (node (ref "GND6") (pin "1") (pinfunction "P_1") (pintype "passive"))
      (node (ref "IC1") (pin "1") (pinfunction "GND_1") (pintype "power_in"))
      (node (ref "IC2") (pin "1") (pinfunction "GND_1") (pintype "power_in"))
      (node (ref "IC3") (pin "1") (pinfunction "GND_1") (pintype "power_in"))
      (node (ref "IC4") (pin "1") (pinfunction "GND_1") (pintype "power_in"))
      (node (ref "IC5") (pin "1") (pinfunction "GND_1") (pintype "power_in"))
      (node (ref "IC6") (pin "1") (pinfunction "GND_1") (pintype "power_in"))
      (node (ref "IC7") (pin "1") (pinfunction "GND_1") (pintype "power_in"))
      (node (ref "IC8") (pin "1") (pinfunction "GND_1") (pintype "power_in"))
      (node (ref "IC9") (pin "1") (pinfunction "GND_1") (pintype "power_in"))
      (node (ref "LED10") (pin "C") (pinfunction "C_C") (pintype "passive"))
      (node (ref "LED11") (pin "C") (pinfunction "C_C") (pintype "passive"))
      (node (ref "LED12") (pin "C") (pinfunction "C_C") (pintype "passive"))
      (node (ref "LED13") (pin "C") (pinfunction "C_C") (pintype "passive"))
      (node (ref "LED14") (pin "C") (pinfunction "C_C") (pintype "passive"))
      (node (ref "LED15") (pin "C") (pinfunction "C_C") (pintype "passive"))
      (node (ref "LED16") (pin "C") (pinfunction "C_C") (pintype "passive"))
      (node (ref "LED17") (pin "C") (pinfunction "C_C") (pintype "passive"))
      (node (ref "LED18") (pin "C") (pinfunction "C_C") (pintype "passive"))
      (node (ref "PP8E") (pin "A") (pinfunction "1_A") (pintype "bidirectional"))
      (node (ref "PP8E") (pin "AA") (pinfunction "23_AA") (pintype "bidirectional"))
      (node (ref "PP8E") (pin "B") (pinfunction "2_B") (pintype "bidirectional"))
      (node (ref "PP8E") (pin "C") (pinfunction "3_C") (pintype "bidirectional"))
      (node (ref "PP8E") (pin "CC") (pinfunction "25_CC") (pintype "bidirectional"))
      (node (ref "PP8E") (pin "E") (pinfunction "5_E") (pintype "bidirectional"))
      (node (ref "PP8E") (pin "EE") (pinfunction "27_EE") (pintype "bidirectional"))
      (node (ref "PP8E") (pin "H") (pinfunction "7_H") (pintype "bidirectional"))
      (node (ref "PP8E") (pin "HH") (pinfunction "29_HH") (pintype "bidirectional"))
      (node (ref "PP8E") (pin "K") (pinfunction "9_K") (pintype "bidirectional"))
      (node (ref "PP8E") (pin "KK") (pinfunction "31_KK") (pintype "bidirectional"))
      (node (ref "PP8E") (pin "M") (pinfunction "11_M") (pintype "bidirectional"))
      (node (ref "PP8E") (pin "MM") (pinfunction "33_MM") (pintype "bidirectional"))
      (node (ref "PP8E") (pin "P") (pinfunction "13_P") (pintype "bidirectional"))
      (node (ref "PP8E") (pin "PP") (pinfunction "35_PP") (pintype "bidirectional"))
      (node (ref "PP8E") (pin "S") (pinfunction "15_S") (pintype "bidirectional"))
      (node (ref "PP8E") (pin "SS") (pinfunction "37_SS") (pintype "bidirectional"))
      (node (ref "PP8E") (pin "U") (pinfunction "17_U") (pintype "bidirectional"))
      (node (ref "PP8E") (pin "UU") (pinfunction "39_UU") (pintype "bidirectional"))
      (node (ref "PP8E") (pin "VV") (pinfunction "40_VV") (pintype "bidirectional"))
      (node (ref "PP8E") (pin "W") (pinfunction "19_W") (pintype "bidirectional"))
      (node (ref "PP8E") (pin "Y") (pinfunction "21_Y") (pintype "bidirectional"))
      (node (ref "PR8E") (pin "A") (pinfunction "1_A") (pintype "bidirectional"))
      (node (ref "PR8E") (pin "AA") (pinfunction "23_AA") (pintype "bidirectional"))
      (node (ref "PR8E") (pin "B") (pinfunction "2_B") (pintype "bidirectional"))
      (node (ref "PR8E") (pin "C") (pinfunction "3_C") (pintype "bidirectional"))
      (node (ref "PR8E") (pin "CC") (pinfunction "25_CC") (pintype "bidirectional"))
      (node (ref "PR8E") (pin "E") (pinfunction "5_E") (pintype "bidirectional"))
      (node (ref "PR8E") (pin "EE") (pinfunction "27_EE") (pintype "bidirectional"))
      (node (ref "PR8E") (pin "H") (pinfunction "7_H") (pintype "bidirectional"))
      (node (ref "PR8E") (pin "HH") (pinfunction "29_HH") (pintype "bidirectional"))
      (node (ref "PR8E") (pin "J") (pinfunction "8_J") (pintype "bidirectional"))
      (node (ref "PR8E") (pin "K") (pinfunction "9_K") (pintype "bidirectional"))
      (node (ref "PR8E") (pin "KK") (pinfunction "31_KK") (pintype "bidirectional"))
      (node (ref "PR8E") (pin "M") (pinfunction "11_M") (pintype "bidirectional"))
      (node (ref "PR8E") (pin "MM") (pinfunction "33_MM") (pintype "bidirectional"))
      (node (ref "PR8E") (pin "P") (pinfunction "13_P") (pintype "bidirectional"))
      (node (ref "PR8E") (pin "PP") (pinfunction "35_PP") (pintype "bidirectional"))
      (node (ref "PR8E") (pin "S") (pinfunction "15_S") (pintype "bidirectional"))
      (node (ref "PR8E") (pin "SS") (pinfunction "37_SS") (pintype "bidirectional"))
      (node (ref "PR8E") (pin "U") (pinfunction "17_U") (pintype "bidirectional"))
      (node (ref "PR8E") (pin "UU") (pinfunction "39_UU") (pintype "bidirectional"))
      (node (ref "PR8E") (pin "VV") (pinfunction "40_VV") (pintype "bidirectional"))
      (node (ref "PR8E") (pin "W") (pinfunction "19_W") (pintype "bidirectional"))
      (node (ref "PR8E") (pin "Y") (pinfunction "21_Y") (pintype "bidirectional"))
      (node (ref "PWR") (pin "K") (pinfunction "C_K") (pintype "passive"))
      (node (ref "SV1") (pin "1") (pinfunction "1_1") (pintype "passive"))
      (node (ref "SV2") (pin "1") (pinfunction "1_1") (pintype "passive"))
      (node (ref "SV3") (pin "1") (pinfunction "1_1") (pintype "passive"))
      (node (ref "T1") (pin "C") (pinfunction "E_C") (pintype "passive"))
      (node (ref "T2") (pin "C") (pinfunction "E_C") (pintype "passive"))
      (node (ref "T3") (pin "C") (pinfunction "E_C") (pintype "passive"))
      (node (ref "T4") (pin "C") (pinfunction "E_C") (pintype "passive"))
      (node (ref "T5") (pin "C") (pinfunction "E_C") (pintype "passive"))
      (node (ref "T6") (pin "C") (pinfunction "E_C") (pintype "passive"))
      (node (ref "T7") (pin "C") (pinfunction "E_C") (pintype "passive"))
      (node (ref "T8") (pin "C") (pinfunction "E_C") (pintype "passive"))
      (node (ref "T9") (pin "C") (pinfunction "E_C") (pintype "passive"))
      (node (ref "U$2") (pin "GND") (pinfunction "GND_GND") (pintype "power_in"))
      (node (ref "U$2") (pin "GND_1") (pinfunction "GND1_GND_1") (pintype "power_in"))
      (node (ref "U$2") (pin "GND_2") (pinfunction "GND2_GND_2") (pintype "power_in"))
      (node (ref "U$2") (pin "GND_3") (pinfunction "GND_GND_3") (pintype "power_in"))
      (node (ref "U$2") (pin "GND_4") (pinfunction "GND1_GND_4") (pintype "power_in"))
    )
    (net (code "48") (name "Net-(IC1-CON)") (class "Default")
      (node (ref "IC1") (pin "5") (pinfunction "CON_5") (pintype "input"))
      (node (ref "IC2") (pin "5") (pinfunction "CON_5") (pintype "input"))
      (node (ref "IC3") (pin "5") (pinfunction "CON_5") (pintype "input"))
      (node (ref "IC4") (pin "5") (pinfunction "CON_5") (pintype "input"))
      (node (ref "IC5") (pin "5") (pinfunction "CON_5") (pintype "input"))
      (node (ref "IC6") (pin "5") (pinfunction "CON_5") (pintype "input"))
      (node (ref "IC7") (pin "5") (pinfunction "CON_5") (pintype "input"))
      (node (ref "IC8") (pin "5") (pinfunction "CON_5") (pintype "input"))
      (node (ref "IC9") (pin "5") (pinfunction "CON_5") (pintype "input"))
      (node (ref "PWR") (pin "A") (pinfunction "A_A") (pintype "passive"))
      (node (ref "R5") (pin "1") (pinfunction "1_1") (pintype "passive"))
    )
    (net (code "49") (name "Net-(IC1-TRE)") (class "Default")
      (node (ref "IC1") (pin "2") (pinfunction "TRI_2") (pintype "input"))
      (node (ref "IC1") (pin "6") (pinfunction "TRE_6") (pintype "input"))
      (node (ref "RP1") (pin "2") (pinfunction "2_2") (pintype "passive"))
      (node (ref "T1") (pin "A") (pinfunction "C_A") (pintype "passive"))
    )
    (net (code "50") (name "Net-(IC2-TRE)") (class "Default")
      (node (ref "IC2") (pin "2") (pinfunction "TRI_2") (pintype "input"))
      (node (ref "IC2") (pin "6") (pinfunction "TRE_6") (pintype "input"))
      (node (ref "RP1") (pin "3") (pinfunction "2_3") (pintype "passive"))
      (node (ref "T2") (pin "A") (pinfunction "C_A") (pintype "passive"))
    )
    (net (code "51") (name "Net-(IC3-TRE)") (class "Default")
      (node (ref "IC3") (pin "2") (pinfunction "TRI_2") (pintype "input"))
      (node (ref "IC3") (pin "6") (pinfunction "TRE_6") (pintype "input"))
      (node (ref "RP1") (pin "4") (pinfunction "2_4") (pintype "passive"))
      (node (ref "T3") (pin "A") (pinfunction "C_A") (pintype "passive"))
    )
    (net (code "52") (name "Net-(IC4-TRE)") (class "Default")
      (node (ref "IC4") (pin "2") (pinfunction "TRI_2") (pintype "input"))
      (node (ref "IC4") (pin "6") (pinfunction "TRE_6") (pintype "input"))
      (node (ref "RP1") (pin "5") (pinfunction "2_5") (pintype "passive"))
      (node (ref "T4") (pin "A") (pinfunction "C_A") (pintype "passive"))
    )
    (net (code "53") (name "Net-(IC5-TRE)") (class "Default")
      (node (ref "IC5") (pin "2") (pinfunction "TRI_2") (pintype "input"))
      (node (ref "IC5") (pin "6") (pinfunction "TRE_6") (pintype "input"))
      (node (ref "RP1") (pin "6") (pinfunction "2_6") (pintype "passive"))
      (node (ref "T5") (pin "A") (pinfunction "C_A") (pintype "passive"))
    )
    (net (code "54") (name "Net-(IC6-TRE)") (class "Default")
      (node (ref "IC6") (pin "2") (pinfunction "TRI_2") (pintype "input"))
      (node (ref "IC6") (pin "6") (pinfunction "TRE_6") (pintype "input"))
      (node (ref "RP1") (pin "7") (pinfunction "2_7") (pintype "passive"))
      (node (ref "T6") (pin "A") (pinfunction "C_A") (pintype "passive"))
    )
    (net (code "55") (name "Net-(IC7-TRE)") (class "Default")
      (node (ref "IC7") (pin "2") (pinfunction "TRI_2") (pintype "input"))
      (node (ref "IC7") (pin "6") (pinfunction "TRE_6") (pintype "input"))
      (node (ref "RP1") (pin "8") (pinfunction "2_8") (pintype "passive"))
      (node (ref "T7") (pin "A") (pinfunction "C_A") (pintype "passive"))
    )
    (net (code "56") (name "Net-(IC8-TRE)") (class "Default")
      (node (ref "IC8") (pin "2") (pinfunction "TRI_2") (pintype "input"))
      (node (ref "IC8") (pin "6") (pinfunction "TRE_6") (pintype "input"))
      (node (ref "RP1") (pin "9") (pinfunction "2_9") (pintype "passive"))
      (node (ref "T8") (pin "A") (pinfunction "C_A") (pintype "passive"))
    )
    (net (code "57") (name "Net-(IC9-TRE)") (class "Default")
      (node (ref "IC9") (pin "2") (pinfunction "TRI_2") (pintype "input"))
      (node (ref "IC9") (pin "6") (pinfunction "TRE_6") (pintype "input"))
      (node (ref "RP1") (pin "10") (pinfunction "2_10") (pintype "passive"))
      (node (ref "T9") (pin "A") (pinfunction "C_A") (pintype "passive"))
    )
    (net (code "58") (name "Net-(LED10-PadA)") (class "Default")
      (node (ref "LED10") (pin "A") (pinfunction "A_A") (pintype "passive"))
      (node (ref "RP2") (pin "2") (pinfunction "2_2") (pintype "passive"))
    )
    (net (code "59") (name "Net-(RP2B-2)") (class "Default")
      (node (ref "LED11") (pin "A") (pinfunction "A_A") (pintype "passive"))
      (node (ref "RP2") (pin "3") (pinfunction "2_3") (pintype "passive"))
    )
    (net (code "60") (name "Net-(RP2C-2)") (class "Default")
      (node (ref "LED12") (pin "A") (pinfunction "A_A") (pintype "passive"))
      (node (ref "RP2") (pin "4") (pinfunction "2_4") (pintype "passive"))
    )
    (net (code "61") (name "Net-(RP2D-2)") (class "Default")
      (node (ref "LED13") (pin "A") (pinfunction "A_A") (pintype "passive"))
      (node (ref "RP2") (pin "5") (pinfunction "2_5") (pintype "passive"))
    )
    (net (code "62") (name "Net-(RP2E-2)") (class "Default")
      (node (ref "LED14") (pin "A") (pinfunction "A_A") (pintype "passive"))
      (node (ref "RP2") (pin "6") (pinfunction "2_6") (pintype "passive"))
    )
    (net (code "63") (name "Net-(RP2F-2)") (class "Default")
      (node (ref "LED15") (pin "A") (pinfunction "A_A") (pintype "passive"))
      (node (ref "RP2") (pin "7") (pinfunction "2_7") (pintype "passive"))
    )
    (net (code "64") (name "Net-(RP2G-2)") (class "Default")
      (node (ref "LED16") (pin "A") (pinfunction "A_A") (pintype "passive"))
      (node (ref "RP2") (pin "8") (pinfunction "2_8") (pintype "passive"))
    )
    (net (code "65") (name "Net-(RP2H-2)") (class "Default")
      (node (ref "LED17") (pin "A") (pinfunction "A_A") (pintype "passive"))
      (node (ref "RP2") (pin "9") (pinfunction "2_9") (pintype "passive"))
    )
    (net (code "66") (name "Net-(RP2I-2)") (class "Default")
      (node (ref "LED18") (pin "A") (pinfunction "A_A") (pintype "passive"))
      (node (ref "RP2") (pin "10") (pinfunction "2_10") (pintype "passive"))
    )
    (net (code "67") (name "Net-(U$2B-+5V)") (class "Default")
      (node (ref "U$2") (pin "5V0_1") (pinfunction "+5V_5V0_1") (pintype "power_in"))
      (node (ref "U$2") (pin "5V0_2") (pinfunction "+5V0_5V0_2") (pintype "power_in"))
    )
    (net (code "68") (name "VCC") (class "Default")
      (node (ref "C1") (pin "1") (pinfunction "1_1") (pintype "passive"))
      (node (ref "C2") (pin "1") (pinfunction "1_1") (pintype "passive"))
      (node (ref "IC1") (pin "4") (pinfunction "/RES_4") (pintype "input"))
      (node (ref "IC1") (pin "8") (pinfunction "VCC+_8") (pintype "power_in"))
      (node (ref "IC2") (pin "4") (pinfunction "/RES_4") (pintype "input"))
      (node (ref "IC2") (pin "8") (pinfunction "VCC+_8") (pintype "power_in"))
      (node (ref "IC3") (pin "4") (pinfunction "/RES_4") (pintype "input"))
      (node (ref "IC3") (pin "8") (pinfunction "VCC+_8") (pintype "power_in"))
      (node (ref "IC4") (pin "4") (pinfunction "/RES_4") (pintype "input"))
      (node (ref "IC4") (pin "8") (pinfunction "VCC+_8") (pintype "power_in"))
      (node (ref "IC5") (pin "4") (pinfunction "/RES_4") (pintype "input"))
      (node (ref "IC5") (pin "8") (pinfunction "VCC+_8") (pintype "power_in"))
      (node (ref "IC6") (pin "4") (pinfunction "/RES_4") (pintype "input"))
      (node (ref "IC6") (pin "8") (pinfunction "VCC+_8") (pintype "power_in"))
      (node (ref "IC7") (pin "4") (pinfunction "/RES_4") (pintype "input"))
      (node (ref "IC7") (pin "8") (pinfunction "VCC+_8") (pintype "power_in"))
      (node (ref "IC8") (pin "4") (pinfunction "/RES_4") (pintype "input"))
      (node (ref "IC8") (pin "8") (pinfunction "VCC+_8") (pintype "power_in"))
      (node (ref "IC9") (pin "4") (pinfunction "/RES_4") (pintype "input"))
      (node (ref "IC9") (pin "8") (pinfunction "VCC+_8") (pintype "power_in"))
      (node (ref "R5") (pin "2") (pinfunction "2_2") (pintype "passive"))
      (node (ref "RP1") (pin "1") (pinfunction "1_1") (pintype "passive"))
      (node (ref "RP2") (pin "1") (pinfunction "1_1") (pintype "passive"))
      (node (ref "SV1") (pin "7") (pinfunction "7_7") (pintype "passive"))
      (node (ref "SV2") (pin "7") (pinfunction "7_7") (pintype "passive"))
      (node (ref "SV3") (pin "7") (pinfunction "7_7") (pintype "passive"))
      (node (ref "U$2") (pin "5V0") (pinfunction "5V_5V0") (pintype "power_in"))
    )
    (net (code "69") (name "unconnected-(IC1-DIS-Pad7)") (class "Default")
      (node (ref "IC1") (pin "7") (pinfunction "DIS_7") (pintype "output"))
    )
    (net (code "70") (name "unconnected-(IC2-DIS-Pad7)") (class "Default")
      (node (ref "IC2") (pin "7") (pinfunction "DIS_7") (pintype "output"))
    )
    (net (code "71") (name "unconnected-(IC3-DIS-Pad7)") (class "Default")
      (node (ref "IC3") (pin "7") (pinfunction "DIS_7") (pintype "output"))
    )
    (net (code "72") (name "unconnected-(IC4-DIS-Pad7)") (class "Default")
      (node (ref "IC4") (pin "7") (pinfunction "DIS_7") (pintype "output"))
    )
    (net (code "73") (name "unconnected-(IC5-DIS-Pad7)") (class "Default")
      (node (ref "IC5") (pin "7") (pinfunction "DIS_7") (pintype "output"))
    )
    (net (code "74") (name "unconnected-(IC6-DIS-Pad7)") (class "Default")
      (node (ref "IC6") (pin "7") (pinfunction "DIS_7") (pintype "output"))
    )
    (net (code "75") (name "unconnected-(IC7-DIS-Pad7)") (class "Default")
      (node (ref "IC7") (pin "7") (pinfunction "DIS_7") (pintype "output"))
    )
    (net (code "76") (name "unconnected-(IC8-DIS-Pad7)") (class "Default")
      (node (ref "IC8") (pin "7") (pinfunction "DIS_7") (pintype "output"))
    )
    (net (code "77") (name "unconnected-(IC9-DIS-Pad7)") (class "Default")
      (node (ref "IC9") (pin "7") (pinfunction "DIS_7") (pintype "output"))
    )
    (net (code "78") (name "unconnected-(PP8E-10-PadL)") (class "Default")
      (node (ref "PP8E") (pin "L") (pinfunction "10_L") (pintype "bidirectional"))
    )
    (net (code "79") (name "unconnected-(PP8E-34-PadNN)") (class "Default")
      (node (ref "PP8E") (pin "NN") (pinfunction "34_NN") (pintype "bidirectional"))
    )
    (net (code "80") (name "unconnected-(PP8E-36-PadRR)") (class "Default")
      (node (ref "PP8E") (pin "RR") (pinfunction "36_RR") (pintype "bidirectional"))
    )
    (net (code "81") (name "unconnected-(PP8E-38-PadTT)") (class "Default")
      (node (ref "PP8E") (pin "TT") (pinfunction "38_TT") (pintype "bidirectional"))
    )
    (net (code "82") (name "unconnected-(PR8E-4-PadD)") (class "Default")
      (node (ref "PR8E") (pin "D") (pinfunction "4_D") (pintype "bidirectional"))
    )
    (net (code "83") (name "unconnected-(SV4-Pad1)") (class "Default")
      (node (ref "SV4") (pin "1") (pinfunction "1_1") (pintype "passive"))
    )
    (net (code "84") (name "unconnected-(SV4-Pad2)") (class "Default")
      (node (ref "SV4") (pin "2") (pinfunction "2_2") (pintype "passive"))
    )
    (net (code "85") (name "unconnected-(SV4-Pad3)") (class "Default")
      (node (ref "SV4") (pin "3") (pinfunction "3_3") (pintype "passive"))
    )
    (net (code "86") (name "unconnected-(SV4-Pad4)") (class "Default")
      (node (ref "SV4") (pin "4") (pinfunction "4_4") (pintype "passive"))
    )
    (net (code "87") (name "unconnected-(SV4-Pad5)") (class "Default")
      (node (ref "SV4") (pin "5") (pinfunction "5_5") (pintype "passive"))
    )
    (net (code "88") (name "unconnected-(SV4-Pad6)") (class "Default")
      (node (ref "SV4") (pin "6") (pinfunction "6_6") (pintype "passive"))
    )
    (net (code "89") (name "unconnected-(SV4-Pad7)") (class "Default")
      (node (ref "SV4") (pin "7") (pinfunction "7_7") (pintype "passive"))
    )
    (net (code "90") (name "unconnected-(SV4-Pad8)") (class "Default")
      (node (ref "SV4") (pin "8") (pinfunction "8_8") (pintype "passive"))
    )
    (net (code "91") (name "unconnected-(SV4-Pad9)") (class "Default")
      (node (ref "SV4") (pin "9") (pinfunction "9_9") (pintype "passive"))
    )
    (net (code "92") (name "unconnected-(SV4-Pad10)") (class "Default")
      (node (ref "SV4") (pin "10") (pinfunction "10_10") (pintype "passive"))
    )
    (net (code "93") (name "unconnected-(SV5-Pad1)") (class "Default")
      (node (ref "SV5") (pin "1") (pinfunction "1_1") (pintype "passive"))
    )
    (net (code "94") (name "unconnected-(SV5-Pad2)") (class "Default")
      (node (ref "SV5") (pin "2") (pinfunction "2_2") (pintype "passive"))
    )
    (net (code "95") (name "unconnected-(SV5-Pad3)") (class "Default")
      (node (ref "SV5") (pin "3") (pinfunction "3_3") (pintype "passive"))
    )
    (net (code "96") (name "unconnected-(SV5-Pad4)") (class "Default")
      (node (ref "SV5") (pin "4") (pinfunction "4_4") (pintype "passive"))
    )
    (net (code "97") (name "unconnected-(SV5-Pad5)") (class "Default")
      (node (ref "SV5") (pin "5") (pinfunction "5_5") (pintype "passive"))
    )
    (net (code "98") (name "unconnected-(SV5-Pad6)") (class "Default")
      (node (ref "SV5") (pin "6") (pinfunction "6_6") (pintype "passive"))
    )
    (net (code "99") (name "unconnected-(SV5-Pad7)") (class "Default")
      (node (ref "SV5") (pin "7") (pinfunction "7_7") (pintype "passive"))
    )
    (net (code "100") (name "unconnected-(SV5-Pad8)") (class "Default")
      (node (ref "SV5") (pin "8") (pinfunction "8_8") (pintype "passive"))
    )
    (net (code "101") (name "unconnected-(SV5-Pad9)") (class "Default")
      (node (ref "SV5") (pin "9") (pinfunction "9_9") (pintype "passive"))
    )
    (net (code "102") (name "unconnected-(SV5-Pad10)") (class "Default")
      (node (ref "SV5") (pin "10") (pinfunction "10_10") (pintype "passive"))
    )
    (net (code "103") (name "unconnected-(U$2-Pad22)") (class "Default")
      (node (ref "U$2") (pin "22") (pinfunction "22_22") (pintype "bidirectional"))
    )
    (net (code "104") (name "unconnected-(U$2-Pad30)") (class "Default")
      (node (ref "U$2") (pin "30") (pinfunction "30_30") (pintype "bidirectional"))
    )
    (net (code "105") (name "unconnected-(U$2-PadA5)") (class "Default")
      (node (ref "U$2") (pin "A5") (pinfunction "A5_A5") (pintype "bidirectional"))
    )
    (net (code "106") (name "unconnected-(U$2-PadA6)") (class "Default")
      (node (ref "U$2") (pin "A6") (pinfunction "A6_A6") (pintype "bidirectional"))
    )
    (net (code "107") (name "unconnected-(U$2-PadA7)") (class "Default")
      (node (ref "U$2") (pin "A7") (pinfunction "A7_A7") (pintype "bidirectional"))
    )
    (net (code "108") (name "unconnected-(U$2-PadA8)") (class "Default")
      (node (ref "U$2") (pin "A8") (pinfunction "A8_A8") (pintype "bidirectional"))
    )
    (net (code "109") (name "unconnected-(U$2-PadA9)") (class "Default")
      (node (ref "U$2") (pin "A9") (pinfunction "A9_A9") (pintype "bidirectional"))
    )
    (net (code "110") (name "unconnected-(U$2-PadA10)") (class "Default")
      (node (ref "U$2") (pin "A10") (pinfunction "A10_A10") (pintype "bidirectional"))
    )
    (net (code "111") (name "unconnected-(U$2-PadA11)") (class "Default")
      (node (ref "U$2") (pin "A11") (pinfunction "A11_A11") (pintype "bidirectional"))
    )
    (net (code "112") (name "unconnected-(U$2-PadAREF)") (class "Default")
      (node (ref "U$2") (pin "AREF") (pinfunction "AREF_AREF") (pintype "bidirectional"))
    )
    (net (code "113") (name "unconnected-(U$2-PadCANRX)") (class "Default")
      (node (ref "U$2") (pin "CANRX") (pinfunction "CANRX_CANRX") (pintype "bidirectional"))
    )
    (net (code "114") (name "unconnected-(U$2-PadCANTX)") (class "Default")
      (node (ref "U$2") (pin "CANTX") (pinfunction "CANTX_CANTX") (pintype "bidirectional"))
    )
    (net (code "115") (name "unconnected-(U$2-PadDAC0)") (class "Default")
      (node (ref "U$2") (pin "DAC0") (pinfunction "DAC0_DAC0") (pintype "bidirectional"))
    )
    (net (code "116") (name "unconnected-(U$2-PadDAC1)") (class "Default")
      (node (ref "U$2") (pin "DAC1") (pinfunction "DAC1_DAC1") (pintype "bidirectional"))
    )
    (net (code "117") (name "unconnected-(U$2A-D9-Pad9)") (class "Default")
      (node (ref "U$2") (pin "9") (pinfunction "D9_9") (pintype "bidirectional"))
    )
    (net (code "118") (name "unconnected-(U$2A-D10-Pad10)") (class "Default")
      (node (ref "U$2") (pin "10") (pinfunction "D10_10") (pintype "bidirectional"))
    )
    (net (code "119") (name "unconnected-(U$2A-D11-Pad11)") (class "Default")
      (node (ref "U$2") (pin "11") (pinfunction "D11_11") (pintype "bidirectional"))
    )
    (net (code "120") (name "unconnected-(U$2A-D12-Pad12)") (class "Default")
      (node (ref "U$2") (pin "12") (pinfunction "D12_12") (pintype "bidirectional"))
    )
    (net (code "121") (name "unconnected-(U$2A-D13-Pad13)") (class "Default")
      (node (ref "U$2") (pin "13") (pinfunction "D13_13") (pintype "bidirectional"))
    )
    (net (code "122") (name "unconnected-(U$2A-{slash}RESET-PadRESET)") (class "Default")
      (node (ref "U$2") (pin "RESET") (pinfunction "/RESET_RESET") (pintype "bidirectional"))
    )
    (net (code "123") (name "unconnected-(U$2B-RX119-Pad19)") (class "Default")
      (node (ref "U$2") (pin "19") (pinfunction "RX119_19") (pintype "bidirectional"))
    )
    (net (code "124") (name "unconnected-(U$2B-RX217-Pad17)") (class "Default")
      (node (ref "U$2") (pin "17") (pinfunction "RX217_17") (pintype "bidirectional"))
    )
    (net (code "125") (name "unconnected-(U$2B-RX315-Pad15)") (class "Default")
      (node (ref "U$2") (pin "15") (pinfunction "RX315_15") (pintype "bidirectional"))
    )
    (net (code "126") (name "unconnected-(U$2B-SCL21-Pad21)") (class "Default")
      (node (ref "U$2") (pin "21") (pinfunction "SCL21_21") (pintype "bidirectional"))
    )
    (net (code "127") (name "unconnected-(U$2B-SDA20-Pad20)") (class "Default")
      (node (ref "U$2") (pin "20") (pinfunction "SDA20_20") (pintype "bidirectional"))
    )
    (net (code "128") (name "unconnected-(U$2B-TX118-Pad18)") (class "Default")
      (node (ref "U$2") (pin "18") (pinfunction "TX118_18") (pintype "bidirectional"))
    )
    (net (code "129") (name "unconnected-(U$2B-TX216-Pad16)") (class "Default")
      (node (ref "U$2") (pin "16") (pinfunction "TX216_16") (pintype "bidirectional"))
    )
    (net (code "130") (name "unconnected-(U$2B-TX314-Pad14)") (class "Default")
      (node (ref "U$2") (pin "14") (pinfunction "TX314_14") (pintype "bidirectional"))
    )
  )
)
